# BBB-SPI-ADC-GPS-Cape.net
KiCad netlist of a schematic drawn in EAGLE
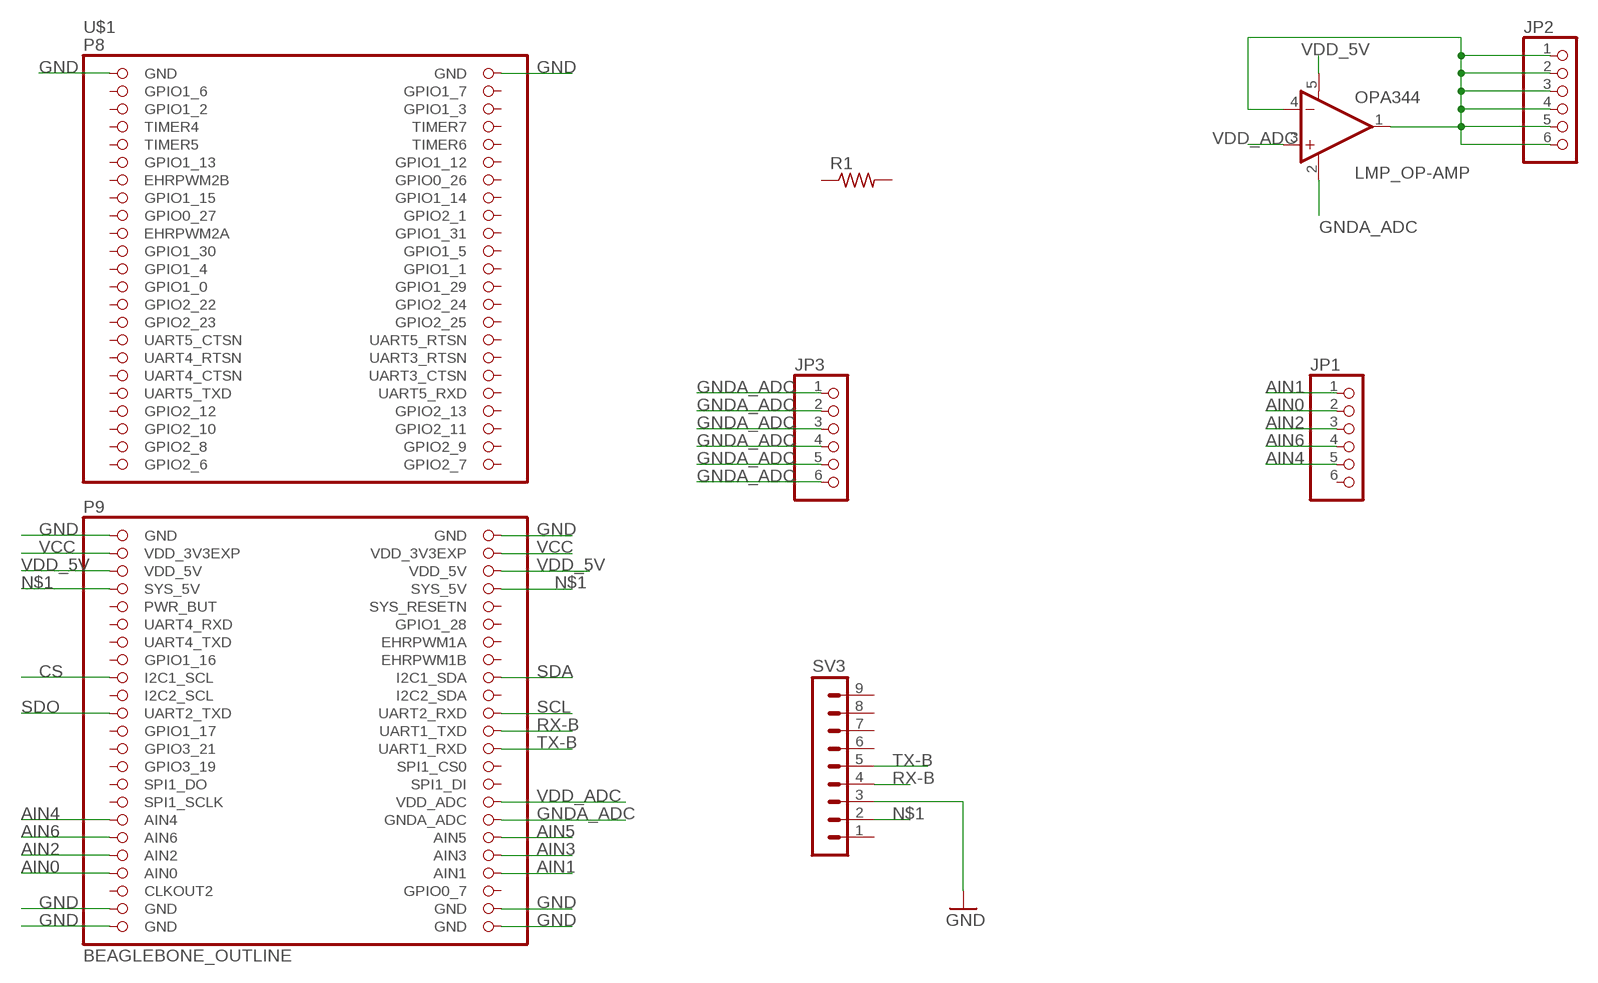
[diagram p0: schematic, sheet 1]

(export (version "E")
  (design (tool "Eeschema 10.0.6"))
  (components
    (comp (ref "JP1")
      (value "PINHD-1X6")
      (footprint "eagle-import:1X06")
      (libsource (lib "eagle-import") (part "PINHD-1X6"))
    )
    (comp (ref "JP2")
      (value "PINHD-1X6")
      (footprint "eagle-import:1X06")
      (libsource (lib "eagle-import") (part "PINHD-1X6"))
    )
    (comp (ref "JP3")
      (value "PINHD-1X6")
      (footprint "eagle-import:1X06")
      (libsource (lib "eagle-import") (part "PINHD-1X6"))
    )
    (comp (ref "LMP_OP-AMP")
      (value "OPA344")
      (footprint "eagle-import:SOT23-5")
      (libsource (lib "eagle-import") (part "OPA344"))
    )
    (comp (ref "R1")
      (value "RES-US1206FAB")
      (footprint "eagle-import:R1206FAB")
      (libsource (lib "eagle-import") (part "RES-US1206FAB"))
    )
    (comp (ref "SV3")
      (value "MA09-1")
      (footprint "eagle-import:MA09-1")
      (libsource (lib "eagle-import") (part "MA09-1"))
    )
    (comp (ref "U$1")
      (value "BEAGLEBONE_OUTLINE")
      (footprint "eagle-import:BEAGLEBONE_SHIELD")
      (libsource (lib "eagle-import") (part "BEAGLEBONE_OUTLINE"))
    )
  )
  (nets
    (net (code "1") (name "/AIN0") (class "Default")
      (node (ref "JP1") (pin "2") (pinfunction "2_2") (pintype "passive"))
      (node (ref "U$1") (pin "85") (pinfunction "AIN0_85") (pintype "power_in"))
    )
    (net (code "2") (name "/AIN1") (class "Default")
      (node (ref "JP1") (pin "1") (pinfunction "1_1") (pintype "passive"))
      (node (ref "U$1") (pin "86") (pinfunction "AIN1_86") (pintype "passive"))
    )
    (net (code "3") (name "/AIN2") (class "Default")
      (node (ref "JP1") (pin "3") (pinfunction "3_3") (pintype "passive"))
      (node (ref "U$1") (pin "83") (pinfunction "AIN2_83") (pintype "passive"))
    )
    (net (code "4") (name "/AIN3") (class "Default")
      (node (ref "U$1") (pin "84") (pinfunction "AIN3_84") (pintype "passive"))
    )
    (net (code "5") (name "/AIN4") (class "Default")
      (node (ref "JP1") (pin "5") (pinfunction "5_5") (pintype "passive"))
      (node (ref "U$1") (pin "79") (pinfunction "AIN4_79") (pintype "passive"))
    )
    (net (code "6") (name "/AIN5") (class "Default")
      (node (ref "U$1") (pin "82") (pinfunction "AIN5_82") (pintype "passive"))
    )
    (net (code "7") (name "/AIN6") (class "Default")
      (node (ref "JP1") (pin "4") (pinfunction "4_4") (pintype "passive"))
      (node (ref "U$1") (pin "81") (pinfunction "AIN6_81") (pintype "passive"))
    )
    (net (code "8") (name "/CS") (class "Default")
      (node (ref "U$1") (pin "63") (pinfunction "I2C1_SCL_63") (pintype "passive"))
    )
    (net (code "9") (name "/GNDA_ADC") (class "Default")
      (node (ref "JP3") (pin "1") (pinfunction "1_1") (pintype "passive"))
      (node (ref "JP3") (pin "2") (pinfunction "2_2") (pintype "passive"))
      (node (ref "JP3") (pin "3") (pinfunction "3_3") (pintype "passive"))
      (node (ref "JP3") (pin "4") (pinfunction "4_4") (pintype "passive"))
      (node (ref "JP3") (pin "5") (pinfunction "5_5") (pintype "passive"))
      (node (ref "JP3") (pin "6") (pinfunction "6_6") (pintype "passive"))
      (node (ref "LMP_OP-AMP") (pin "2") (pinfunction "V-_2") (pintype "power_in"))
      (node (ref "U$1") (pin "80") (pinfunction "GNDA_ADC_80") (pintype "passive"))
    )
    (net (code "10") (name "/N$1") (class "Default")
      (node (ref "SV3") (pin "2") (pinfunction "2_2") (pintype "passive"))
      (node (ref "U$1") (pin "53") (pinfunction "SYS_5V_53") (pintype "power_in"))
      (node (ref "U$1") (pin "54") (pinfunction "SYS_5V_54") (pintype "passive"))
    )
    (net (code "11") (name "/RX-B") (class "Default")
      (node (ref "SV3") (pin "4") (pinfunction "4_4") (pintype "passive"))
      (node (ref "U$1") (pin "70") (pinfunction "UART1_TXD_70") (pintype "passive"))
    )
    (net (code "12") (name "/SCL") (class "Default")
      (node (ref "U$1") (pin "68") (pinfunction "UART2_RXD_68") (pintype "passive"))
    )
    (net (code "13") (name "/SDA") (class "Default")
      (node (ref "U$1") (pin "64") (pinfunction "I2C1_SDA_64") (pintype "passive"))
    )
    (net (code "14") (name "/SDO") (class "Default")
      (node (ref "U$1") (pin "67") (pinfunction "UART2_TXD_67") (pintype "passive"))
    )
    (net (code "15") (name "/TX-B") (class "Default")
      (node (ref "SV3") (pin "5") (pinfunction "5_5") (pintype "passive"))
      (node (ref "U$1") (pin "72") (pinfunction "UART1_RXD_72") (pintype "passive"))
    )
    (net (code "16") (name "/VCC") (class "Default")
      (node (ref "U$1") (pin "49") (pinfunction "VDD_3V3EXP_49") (pintype "power_in"))
      (node (ref "U$1") (pin "50") (pinfunction "VDD_3V3EXP_50") (pintype "power_in"))
    )
    (net (code "17") (name "/VDD_5V") (class "Default")
      (node (ref "LMP_OP-AMP") (pin "5") (pinfunction "V+_5") (pintype "power_in"))
      (node (ref "U$1") (pin "51") (pinfunction "VDD_5V_51") (pintype "power_in"))
      (node (ref "U$1") (pin "52") (pinfunction "VDD_5V_52") (pintype "power_in"))
    )
    (net (code "18") (name "/VDD_ADC") (class "Default")
      (node (ref "LMP_OP-AMP") (pin "3") (pinfunction "+IN_3") (pintype "input"))
      (node (ref "U$1") (pin "78") (pinfunction "VDD_ADC_78") (pintype "passive"))
    )
    (net (code "19") (name "GND") (class "Default")
      (node (ref "SV3") (pin "3") (pinfunction "3_3") (pintype "passive"))
      (node (ref "U$1") (pin "1") (pinfunction "GND_1") (pintype "power_in"))
      (node (ref "U$1") (pin "2") (pinfunction "GND_2") (pintype "power_in"))
      (node (ref "U$1") (pin "47") (pinfunction "GND_47") (pintype "power_in"))
      (node (ref "U$1") (pin "48") (pinfunction "GND_48") (pintype "power_in"))
      (node (ref "U$1") (pin "89") (pinfunction "GND_89") (pintype "power_in"))
      (node (ref "U$1") (pin "90") (pinfunction "GND_90") (pintype "power_in"))
      (node (ref "U$1") (pin "91") (pinfunction "GND_91") (pintype "power_in"))
      (node (ref "U$1") (pin "92") (pinfunction "GND_92") (pintype "power_in"))
    )
    (net (code "20") (name "Net-(LMP_OP-AMP--IN)") (class "Default")
      (node (ref "JP2") (pin "1") (pinfunction "1_1") (pintype "passive"))
      (node (ref "JP2") (pin "2") (pinfunction "2_2") (pintype "passive"))
      (node (ref "JP2") (pin "3") (pinfunction "3_3") (pintype "passive"))
      (node (ref "JP2") (pin "4") (pinfunction "4_4") (pintype "passive"))
      (node (ref "JP2") (pin "5") (pinfunction "5_5") (pintype "passive"))
      (node (ref "JP2") (pin "6") (pinfunction "6_6") (pintype "passive"))
      (node (ref "LMP_OP-AMP") (pin "1") (pinfunction "OUT_1") (pintype "output"))
      (node (ref "LMP_OP-AMP") (pin "4") (pinfunction "-IN_4") (pintype "input"))
    )
    (net (code "21") (name "unconnected-(JP1-Pad6)") (class "Default")
      (node (ref "JP1") (pin "6") (pinfunction "6_6") (pintype "passive"))
    )
    (net (code "22") (name "unconnected-(R1-Pad1)") (class "Default")
      (node (ref "R1") (pin "1") (pinfunction "1_1") (pintype "passive"))
    )
    (net (code "23") (name "unconnected-(R1-Pad2)") (class "Default")
      (node (ref "R1") (pin "2") (pinfunction "2_2") (pintype "passive"))
    )
    (net (code "24") (name "unconnected-(SV3-Pad1)") (class "Default")
      (node (ref "SV3") (pin "1") (pinfunction "1_1") (pintype "passive"))
    )
    (net (code "25") (name "unconnected-(SV3-Pad6)") (class "Default")
      (node (ref "SV3") (pin "6") (pinfunction "6_6") (pintype "passive"))
    )
    (net (code "26") (name "unconnected-(SV3-Pad7)") (class "Default")
      (node (ref "SV3") (pin "7") (pinfunction "7_7") (pintype "passive"))
    )
    (net (code "27") (name "unconnected-(SV3-Pad8)") (class "Default")
      (node (ref "SV3") (pin "8") (pinfunction "8_8") (pintype "passive"))
    )
    (net (code "28") (name "unconnected-(SV3-Pad9)") (class "Default")
      (node (ref "SV3") (pin "9") (pinfunction "9_9") (pintype "passive"))
    )
    (net (code "29") (name "unconnected-(U$1-CLKOUT2-Pad87)") (class "Default")
      (node (ref "U$1") (pin "87") (pinfunction "CLKOUT2_87") (pintype "input"))
    )
    (net (code "30") (name "unconnected-(U$1-EHRPWM1A-Pad60)") (class "Default")
      (node (ref "U$1") (pin "60") (pinfunction "EHRPWM1A_60") (pintype "passive"))
    )
    (net (code "31") (name "unconnected-(U$1-EHRPWM1B-Pad62)") (class "Default")
      (node (ref "U$1") (pin "62") (pinfunction "EHRPWM1B_62") (pintype "passive"))
    )
    (net (code "32") (name "unconnected-(U$1-EHRPWM2A-Pad19)") (class "Default")
      (node (ref "U$1") (pin "19") (pinfunction "EHRPWM2A_19") (pintype "passive"))
    )
    (net (code "33") (name "unconnected-(U$1-EHRPWM2B-Pad13)") (class "Default")
      (node (ref "U$1") (pin "13") (pinfunction "EHRPWM2B_13") (pintype "passive"))
    )
    (net (code "34") (name "unconnected-(U$1-GPIO0_7-Pad88)") (class "Default")
      (node (ref "U$1") (pin "88") (pinfunction "GPIO0_7_88") (pintype "passive"))
    )
    (net (code "35") (name "unconnected-(U$1-GPIO0_26-Pad14)") (class "Default")
      (node (ref "U$1") (pin "14") (pinfunction "GPIO0_26_14") (pintype "passive"))
    )
    (net (code "36") (name "unconnected-(U$1-GPIO0_27-Pad17)") (class "Default")
      (node (ref "U$1") (pin "17") (pinfunction "GPIO0_27_17") (pintype "passive"))
    )
    (net (code "37") (name "unconnected-(U$1-GPIO1_0-Pad25)") (class "Default")
      (node (ref "U$1") (pin "25") (pinfunction "GPIO1_0_25") (pintype "passive"))
    )
    (net (code "38") (name "unconnected-(U$1-GPIO1_1-Pad24)") (class "Default")
      (node (ref "U$1") (pin "24") (pinfunction "GPIO1_1_24") (pintype "passive"))
    )
    (net (code "39") (name "unconnected-(U$1-GPIO1_2-Pad5)") (class "Default")
      (node (ref "U$1") (pin "5") (pinfunction "GPIO1_2_5") (pintype "passive"))
    )
    (net (code "40") (name "unconnected-(U$1-GPIO1_3-Pad6)") (class "Default")
      (node (ref "U$1") (pin "6") (pinfunction "GPIO1_3_6") (pintype "passive"))
    )
    (net (code "41") (name "unconnected-(U$1-GPIO1_4-Pad23)") (class "Default")
      (node (ref "U$1") (pin "23") (pinfunction "GPIO1_4_23") (pintype "passive"))
    )
    (net (code "42") (name "unconnected-(U$1-GPIO1_5-Pad22)") (class "Default")
      (node (ref "U$1") (pin "22") (pinfunction "GPIO1_5_22") (pintype "passive"))
    )
    (net (code "43") (name "unconnected-(U$1-GPIO1_6-Pad3)") (class "Default")
      (node (ref "U$1") (pin "3") (pinfunction "GPIO1_6_3") (pintype "passive"))
    )
    (net (code "44") (name "unconnected-(U$1-GPIO1_7-Pad4)") (class "Default")
      (node (ref "U$1") (pin "4") (pinfunction "GPIO1_7_4") (pintype "passive"))
    )
    (net (code "45") (name "unconnected-(U$1-GPIO1_12-Pad12)") (class "Default")
      (node (ref "U$1") (pin "12") (pinfunction "GPIO1_12_12") (pintype "passive"))
    )
    (net (code "46") (name "unconnected-(U$1-GPIO1_13-Pad11)") (class "Default")
      (node (ref "U$1") (pin "11") (pinfunction "GPIO1_13_11") (pintype "passive"))
    )
    (net (code "47") (name "unconnected-(U$1-GPIO1_14-Pad16)") (class "Default")
      (node (ref "U$1") (pin "16") (pinfunction "GPIO1_14_16") (pintype "passive"))
    )
    (net (code "48") (name "unconnected-(U$1-GPIO1_15-Pad15)") (class "Default")
      (node (ref "U$1") (pin "15") (pinfunction "GPIO1_15_15") (pintype "passive"))
    )
    (net (code "49") (name "unconnected-(U$1-GPIO1_16-Pad61)") (class "Default")
      (node (ref "U$1") (pin "61") (pinfunction "GPIO1_16_61") (pintype "passive"))
    )
    (net (code "50") (name "unconnected-(U$1-GPIO1_17-Pad69)") (class "Default")
      (node (ref "U$1") (pin "69") (pinfunction "GPIO1_17_69") (pintype "passive"))
    )
    (net (code "51") (name "unconnected-(U$1-GPIO1_28-Pad58)") (class "Default")
      (node (ref "U$1") (pin "58") (pinfunction "GPIO1_28_58") (pintype "passive"))
    )
    (net (code "52") (name "unconnected-(U$1-GPIO1_29-Pad26)") (class "Default")
      (node (ref "U$1") (pin "26") (pinfunction "GPIO1_29_26") (pintype "passive"))
    )
    (net (code "53") (name "unconnected-(U$1-GPIO1_30-Pad21)") (class "Default")
      (node (ref "U$1") (pin "21") (pinfunction "GPIO1_30_21") (pintype "passive"))
    )
    (net (code "54") (name "unconnected-(U$1-GPIO1_31-Pad20)") (class "Default")
      (node (ref "U$1") (pin "20") (pinfunction "GPIO1_31_20") (pintype "passive"))
    )
    (net (code "55") (name "unconnected-(U$1-GPIO2_1-Pad18)") (class "Default")
      (node (ref "U$1") (pin "18") (pinfunction "GPIO2_1_18") (pintype "passive"))
    )
    (net (code "56") (name "unconnected-(U$1-GPIO2_6-Pad45)") (class "Default")
      (node (ref "U$1") (pin "45") (pinfunction "GPIO2_6_45") (pintype "passive"))
    )
    (net (code "57") (name "unconnected-(U$1-GPIO2_7-Pad46)") (class "Default")
      (node (ref "U$1") (pin "46") (pinfunction "GPIO2_7_46") (pintype "passive"))
    )
    (net (code "58") (name "unconnected-(U$1-GPIO2_8-Pad43)") (class "Default")
      (node (ref "U$1") (pin "43") (pinfunction "GPIO2_8_43") (pintype "passive"))
    )
    (net (code "59") (name "unconnected-(U$1-GPIO2_9-Pad44)") (class "Default")
      (node (ref "U$1") (pin "44") (pinfunction "GPIO2_9_44") (pintype "passive"))
    )
    (net (code "60") (name "unconnected-(U$1-GPIO2_10-Pad41)") (class "Default")
      (node (ref "U$1") (pin "41") (pinfunction "GPIO2_10_41") (pintype "passive"))
    )
    (net (code "61") (name "unconnected-(U$1-GPIO2_11-Pad42)") (class "Default")
      (node (ref "U$1") (pin "42") (pinfunction "GPIO2_11_42") (pintype "passive"))
    )
    (net (code "62") (name "unconnected-(U$1-GPIO2_12-Pad39)") (class "Default")
      (node (ref "U$1") (pin "39") (pinfunction "GPIO2_12_39") (pintype "passive"))
    )
    (net (code "63") (name "unconnected-(U$1-GPIO2_13-Pad40)") (class "Default")
      (node (ref "U$1") (pin "40") (pinfunction "GPIO2_13_40") (pintype "passive"))
    )
    (net (code "64") (name "unconnected-(U$1-GPIO2_22-Pad27)") (class "Default")
      (node (ref "U$1") (pin "27") (pinfunction "GPIO2_22_27") (pintype "passive"))
    )
    (net (code "65") (name "unconnected-(U$1-GPIO2_23-Pad29)") (class "Default")
      (node (ref "U$1") (pin "29") (pinfunction "GPIO2_23_29") (pintype "passive"))
    )
    (net (code "66") (name "unconnected-(U$1-GPIO2_24-Pad28)") (class "Default")
      (node (ref "U$1") (pin "28") (pinfunction "GPIO2_24_28") (pintype "passive"))
    )
    (net (code "67") (name "unconnected-(U$1-GPIO2_25-Pad30)") (class "Default")
      (node (ref "U$1") (pin "30") (pinfunction "GPIO2_25_30") (pintype "passive"))
    )
    (net (code "68") (name "unconnected-(U$1-GPIO3_19-Pad73)") (class "Default")
      (node (ref "U$1") (pin "73") (pinfunction "GPIO3_19_73") (pintype "passive"))
    )
    (net (code "69") (name "unconnected-(U$1-GPIO3_21-Pad71)") (class "Default")
      (node (ref "U$1") (pin "71") (pinfunction "GPIO3_21_71") (pintype "passive"))
    )
    (net (code "70") (name "unconnected-(U$1-I2C2_SCL-Pad65)") (class "Default")
      (node (ref "U$1") (pin "65") (pinfunction "I2C2_SCL_65") (pintype "passive"))
    )
    (net (code "71") (name "unconnected-(U$1-I2C2_SDA-Pad66)") (class "Default")
      (node (ref "U$1") (pin "66") (pinfunction "I2C2_SDA_66") (pintype "passive"))
    )
    (net (code "72") (name "unconnected-(U$1-PWR_BUT-Pad55)") (class "Default")
      (node (ref "U$1") (pin "55") (pinfunction "PWR_BUT_55") (pintype "passive"))
    )
    (net (code "73") (name "unconnected-(U$1-SPI1_CS0-Pad74)") (class "Default")
      (node (ref "U$1") (pin "74") (pinfunction "SPI1_CS0_74") (pintype "passive"))
    )
    (net (code "74") (name "unconnected-(U$1-SPI1_DI-Pad76)") (class "Default")
      (node (ref "U$1") (pin "76") (pinfunction "SPI1_DI_76") (pintype "passive"))
    )
    (net (code "75") (name "unconnected-(U$1-SPI1_DO-Pad75)") (class "Default")
      (node (ref "U$1") (pin "75") (pinfunction "SPI1_DO_75") (pintype "passive"))
    )
    (net (code "76") (name "unconnected-(U$1-SPI1_SCLK-Pad77)") (class "Default")
      (node (ref "U$1") (pin "77") (pinfunction "SPI1_SCLK_77") (pintype "passive"))
    )
    (net (code "77") (name "unconnected-(U$1-SYS_RESETN-Pad56)") (class "Default")
      (node (ref "U$1") (pin "56") (pinfunction "SYS_RESETN_56") (pintype "passive"))
    )
    (net (code "78") (name "unconnected-(U$1-TIMER4-Pad7)") (class "Default")
      (node (ref "U$1") (pin "7") (pinfunction "TIMER4_7") (pintype "passive"))
    )
    (net (code "79") (name "unconnected-(U$1-TIMER5-Pad9)") (class "Default")
      (node (ref "U$1") (pin "9") (pinfunction "TIMER5_9") (pintype "passive"))
    )
    (net (code "80") (name "unconnected-(U$1-TIMER6-Pad10)") (class "Default")
      (node (ref "U$1") (pin "10") (pinfunction "TIMER6_10") (pintype "passive"))
    )
    (net (code "81") (name "unconnected-(U$1-TIMER7-Pad8)") (class "Default")
      (node (ref "U$1") (pin "8") (pinfunction "TIMER7_8") (pintype "passive"))
    )
    (net (code "82") (name "unconnected-(U$1-UART3_CTSN-Pad36)") (class "Default")
      (node (ref "U$1") (pin "36") (pinfunction "UART3_CTSN_36") (pintype "passive"))
    )
    (net (code "83") (name "unconnected-(U$1-UART3_RTSN-Pad34)") (class "Default")
      (node (ref "U$1") (pin "34") (pinfunction "UART3_RTSN_34") (pintype "passive"))
    )
    (net (code "84") (name "unconnected-(U$1-UART4_CTSN-Pad35)") (class "Default")
      (node (ref "U$1") (pin "35") (pinfunction "UART4_CTSN_35") (pintype "passive"))
    )
    (net (code "85") (name "unconnected-(U$1-UART4_RTSN-Pad33)") (class "Default")
      (node (ref "U$1") (pin "33") (pinfunction "UART4_RTSN_33") (pintype "passive"))
    )
    (net (code "86") (name "unconnected-(U$1-UART4_RXD-Pad57)") (class "Default")
      (node (ref "U$1") (pin "57") (pinfunction "UART4_RXD_57") (pintype "passive"))
    )
    (net (code "87") (name "unconnected-(U$1-UART4_TXD-Pad59)") (class "Default")
      (node (ref "U$1") (pin "59") (pinfunction "UART4_TXD_59") (pintype "passive"))
    )
    (net (code "88") (name "unconnected-(U$1-UART5_CTSN-Pad31)") (class "Default")
      (node (ref "U$1") (pin "31") (pinfunction "UART5_CTSN_31") (pintype "passive"))
    )
    (net (code "89") (name "unconnected-(U$1-UART5_RTSN-Pad32)") (class "Default")
      (node (ref "U$1") (pin "32") (pinfunction "UART5_RTSN_32") (pintype "passive"))
    )
    (net (code "90") (name "unconnected-(U$1-UART5_RXD-Pad38)") (class "Default")
      (node (ref "U$1") (pin "38") (pinfunction "UART5_RXD_38") (pintype "passive"))
    )
    (net (code "91") (name "unconnected-(U$1-UART5_TXD-Pad37)") (class "Default")
      (node (ref "U$1") (pin "37") (pinfunction "UART5_TXD_37") (pintype "passive"))
    )
  )
)
